# main.net
KiCad netlist of a schematic drawn in Altium Designer
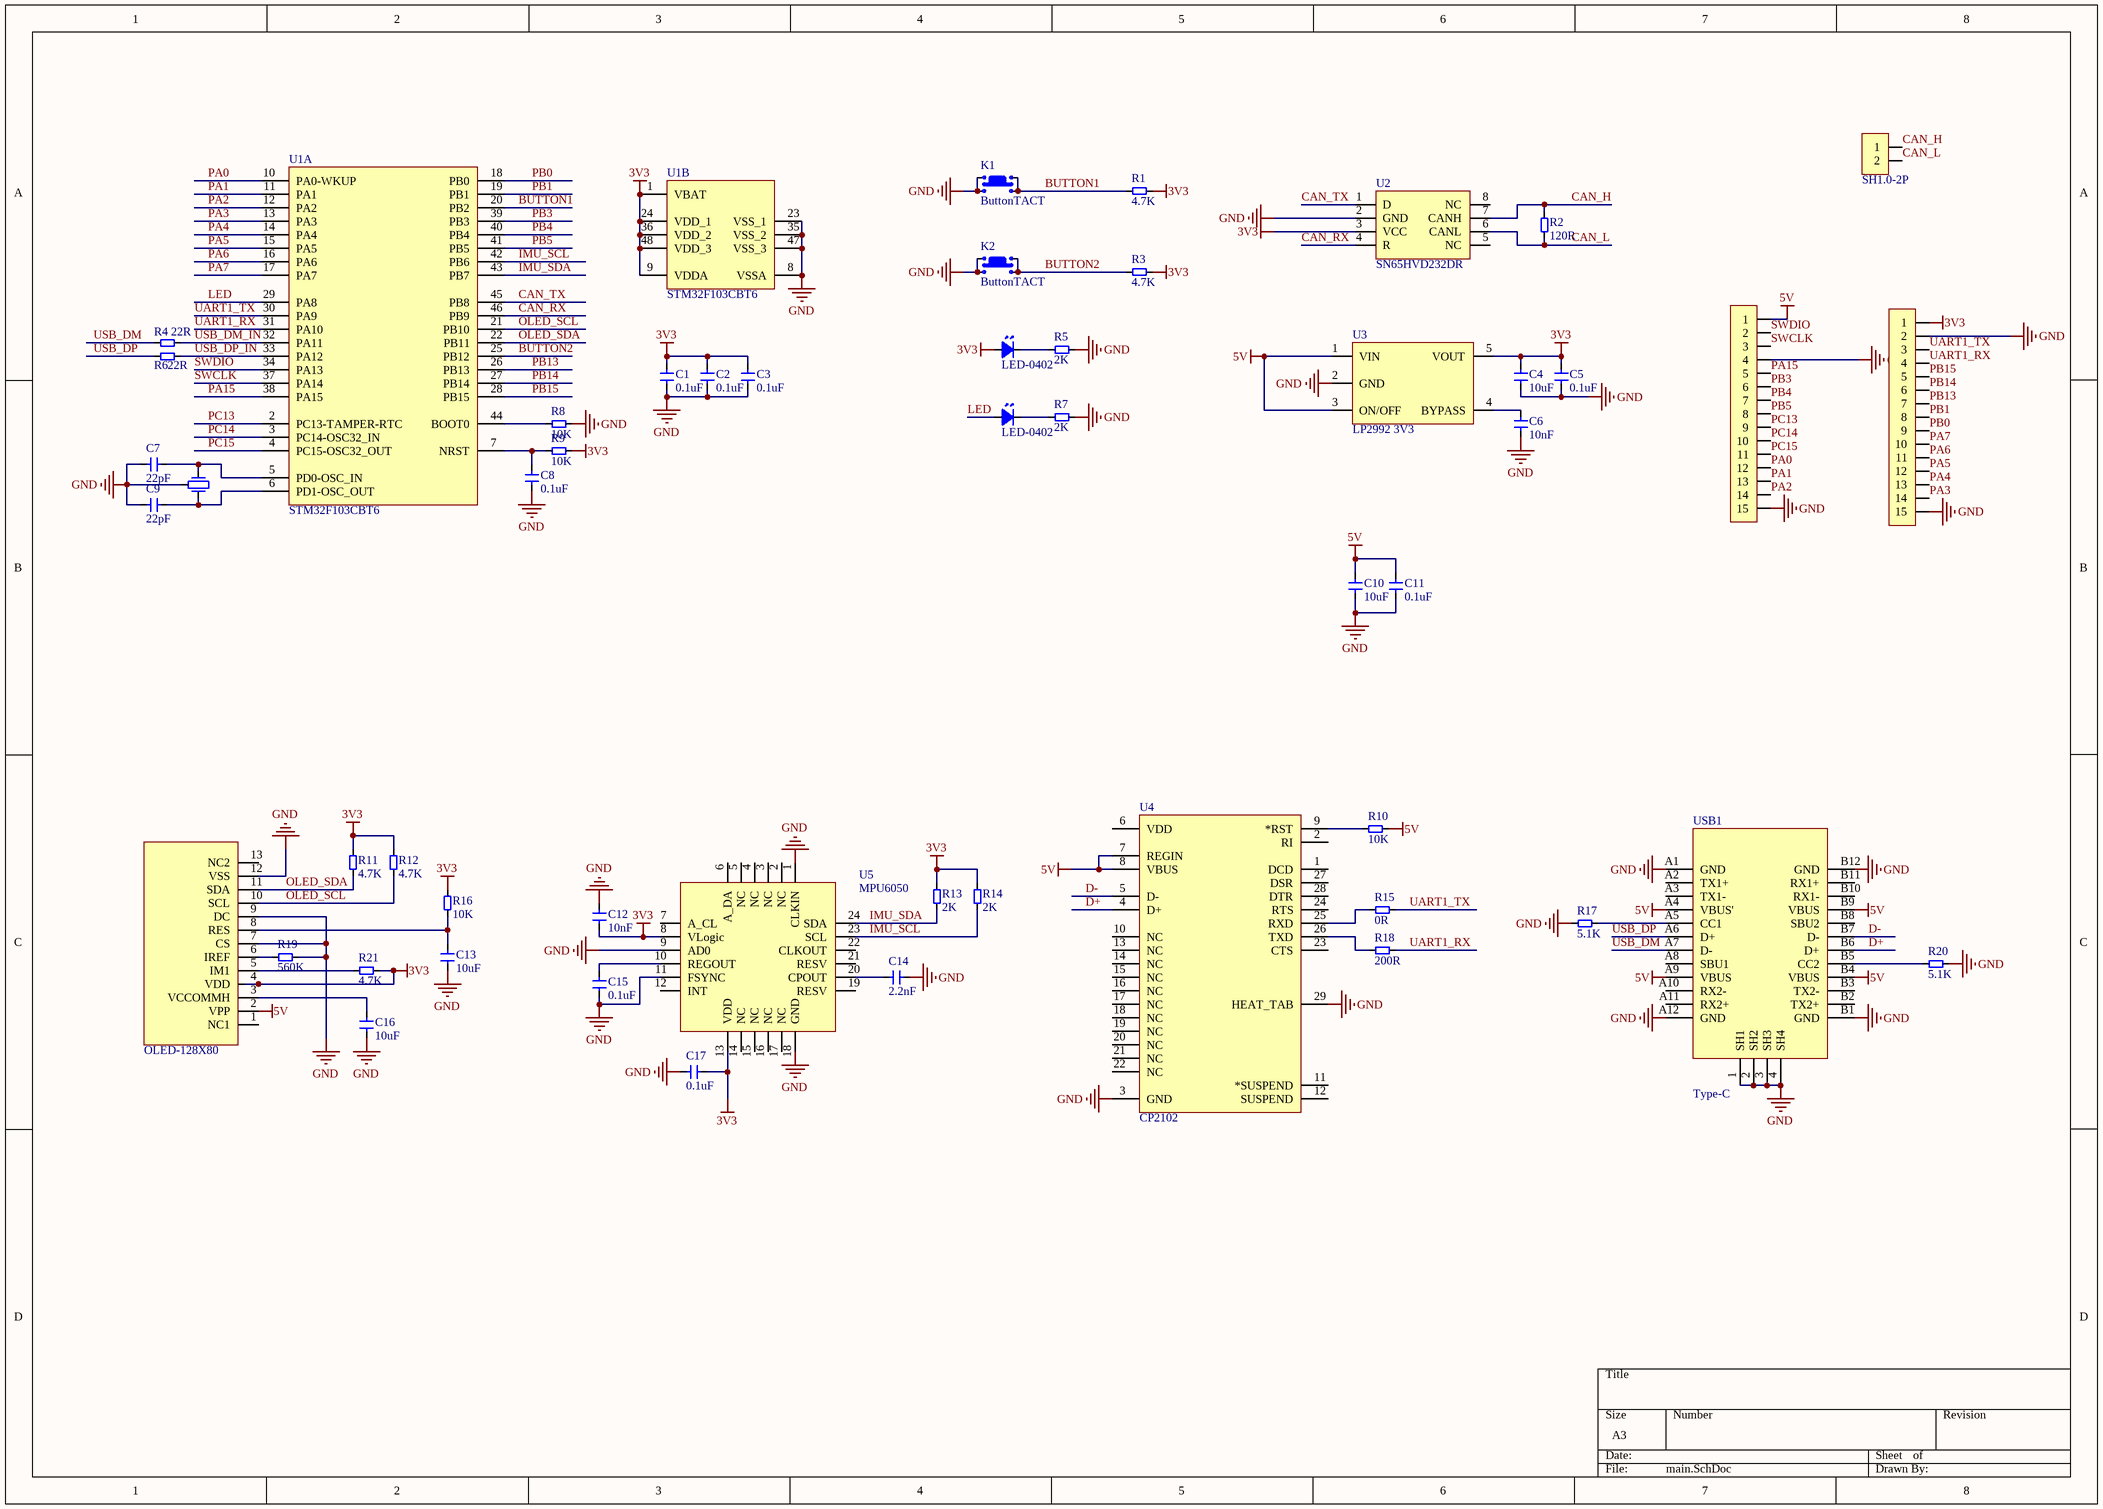
[diagram p0: main.SchDoc]

(export (version "E")
  (design (tool "Eeschema 10.0.6"))
  (components
    (comp (ref "*1")
      (value "SH1.0-2P")
      (footprint "SH1.0-2P")
      (libsource (lib "MySchlib1") (part "SH1.0-2P"))
    )
    (comp (ref "*2")
      (value "LED-0402")
      (footprint "LED_0402_YELLOW")
      (libsource (lib "MySchlib1") (part "LED-0402"))
    )
    (comp (ref "*3")
      (value "LED-0402")
      (footprint "LED_0402_YELLOW")
      (libsource (lib "MySchlib1") (part "LED-0402"))
    )
    (comp (ref "*4")
      (value "OSC-8MHz-3P")
      (footprint "晶振_3P")
      (libsource (lib "MySchlib1") (part "OSC-8MHz-3P"))
    )
    (comp (ref "*5")
      (value "HDR2.54-15P")
      (footprint "HDR2.54-15P")
      (libsource (lib "MySchlib1") (part "HDR2.54-15P"))
    )
    (comp (ref "*6")
      (value "HDR2.54-15P")
      (footprint "HDR2.54-15P")
      (libsource (lib "MySchlib1") (part "HDR2.54-15P"))
    )
    (comp (ref "1")
      (value "OLED-128X80")
      (footprint "OLED-128X80")
      (description "SH1107")
      (libsource (lib "MySchlib1") (part "OLED-128X80"))
    )
    (comp (ref "C1")
      (value "0.1uF")
      (footprint "CAP_0402")
      (description "Cap-0402")
      (libsource (lib "MySchlib1") (part "电容-0402"))
    )
    (comp (ref "C2")
      (value "0.1uF")
      (footprint "CAP_0402")
      (description "Cap-0402")
      (libsource (lib "MySchlib1") (part "电容-0402"))
    )
    (comp (ref "C3")
      (value "0.1uF")
      (footprint "CAP_0402")
      (description "Cap-0402")
      (libsource (lib "MySchlib1") (part "电容-0402"))
    )
    (comp (ref "C4")
      (value "10uF")
      (footprint "CAP_0402")
      (description "Cap-0402")
      (libsource (lib "MySchlib1") (part "电容-0402"))
    )
    (comp (ref "C5")
      (value "0.1uF")
      (footprint "CAP_0402")
      (description "Cap-0402")
      (libsource (lib "MySchlib1") (part "电容-0402"))
    )
    (comp (ref "C6")
      (value "10nF")
      (footprint "CAP_0402")
      (description "Cap-0402")
      (libsource (lib "MySchlib1") (part "电容-0402"))
    )
    (comp (ref "C7")
      (value "22pF")
      (footprint "CAP_0402")
      (description "Cap-0402")
      (libsource (lib "MySchlib1") (part "电容-0402"))
    )
    (comp (ref "C8")
      (value "0.1uF")
      (footprint "CAP_0402")
      (description "Cap-0402")
      (libsource (lib "MySchlib1") (part "电容-0402"))
    )
    (comp (ref "C9")
      (value "22pF")
      (footprint "CAP_0402")
      (description "Cap-0402")
      (libsource (lib "MySchlib1") (part "电容-0402"))
    )
    (comp (ref "C10")
      (value "10uF")
      (footprint "CAP_0402")
      (description "Cap-0402")
      (libsource (lib "MySchlib1") (part "电容-0402"))
    )
    (comp (ref "C11")
      (value "0.1uF")
      (footprint "CAP_0402")
      (description "Cap-0402")
      (libsource (lib "MySchlib1") (part "电容-0402"))
    )
    (comp (ref "C12")
      (value "10nF")
      (footprint "CAP_0402")
      (description "Cap-0402")
      (libsource (lib "MySchlib1") (part "电容-0402"))
    )
    (comp (ref "C13")
      (value "10uF")
      (footprint "CAP_0402")
      (description "Cap-0402")
      (libsource (lib "MySchlib1") (part "电容-0402"))
    )
    (comp (ref "C14")
      (value "2.2nF")
      (footprint "CAP_0402")
      (description "Cap-0402")
      (libsource (lib "MySchlib1") (part "电容-0402"))
    )
    (comp (ref "C15")
      (value "0.1uF")
      (footprint "CAP_0402")
      (description "Cap-0402")
      (libsource (lib "MySchlib1") (part "电容-0402"))
    )
    (comp (ref "C16")
      (value "10uF")
      (footprint "CAP_0402")
      (description "Cap-0402")
      (libsource (lib "MySchlib1") (part "电容-0402"))
    )
    (comp (ref "C17")
      (value "0.1uF")
      (footprint "CAP_0402")
      (description "Cap-0402")
      (libsource (lib "MySchlib1") (part "电容-0402"))
    )
    (comp (ref "K1")
      (value "ButtonTACT")
      (footprint "ButtonTACT_3.5*3.55_90")
      (libsource (lib "MySchlib1") (part "ButtonTACT"))
    )
    (comp (ref "K2")
      (value "ButtonTACT")
      (footprint "ButtonTACT_3.5*3.55_90")
      (libsource (lib "MySchlib1") (part "ButtonTACT"))
    )
    (comp (ref "R1")
      (value "4.7K")
      (footprint "RES_0402")
      (description "Res-0402")
      (libsource (lib "MySchlib1") (part "电阻-0402"))
    )
    (comp (ref "R2")
      (value "120R")
      (footprint "RES_0402")
      (description "Res-0402")
      (libsource (lib "MySchlib1") (part "电阻-0402"))
    )
    (comp (ref "R3")
      (value "4.7K")
      (footprint "RES_0402")
      (description "Res-0402")
      (libsource (lib "MySchlib1") (part "电阻-0402"))
    )
    (comp (ref "R4")
      (value "22R")
      (footprint "RES_0402")
      (description "Res-0402")
      (libsource (lib "MySchlib1") (part "电阻-0402"))
    )
    (comp (ref "R5")
      (value "2K")
      (footprint "RES_0402")
      (description "Res-0402")
      (libsource (lib "MySchlib1") (part "电阻-0402"))
    )
    (comp (ref "R6")
      (value "22R")
      (footprint "RES_0402")
      (description "Res-0402")
      (libsource (lib "MySchlib1") (part "电阻-0402"))
    )
    (comp (ref "R7")
      (value "2K")
      (footprint "RES_0402")
      (description "Res-0402")
      (libsource (lib "MySchlib1") (part "电阻-0402"))
    )
    (comp (ref "R8")
      (value "10K")
      (footprint "RES_0402")
      (description "Res-0402")
      (libsource (lib "MySchlib1") (part "电阻-0402"))
    )
    (comp (ref "R9")
      (value "10K")
      (footprint "RES_0402")
      (description "Res-0402")
      (libsource (lib "MySchlib1") (part "电阻-0402"))
    )
    (comp (ref "R10")
      (value "10K")
      (footprint "RES_0402")
      (description "Res-0402")
      (libsource (lib "MySchlib1") (part "电阻-0402"))
    )
    (comp (ref "R11")
      (value "4.7K")
      (footprint "RES_0402")
      (description "Res-0402")
      (libsource (lib "MySchlib1") (part "电阻-0402"))
    )
    (comp (ref "R12")
      (value "4.7K")
      (footprint "RES_0402")
      (description "Res-0402")
      (libsource (lib "MySchlib1") (part "电阻-0402"))
    )
    (comp (ref "R13")
      (value "2K")
      (footprint "RES_0402")
      (description "Res-0402")
      (libsource (lib "MySchlib1") (part "电阻-0402"))
    )
    (comp (ref "R14")
      (value "2K")
      (footprint "RES_0402")
      (description "Res-0402")
      (libsource (lib "MySchlib1") (part "电阻-0402"))
    )
    (comp (ref "R15")
      (value "0R")
      (footprint "RES_0402")
      (description "Res-0402")
      (libsource (lib "MySchlib1") (part "电阻-0402"))
    )
    (comp (ref "R16")
      (value "10K")
      (footprint "RES_0402")
      (description "Res-0402")
      (libsource (lib "MySchlib1") (part "电阻-0402"))
    )
    (comp (ref "R17")
      (value "5.1K")
      (footprint "RES_0402")
      (description "Res-0402")
      (libsource (lib "MySchlib1") (part "电阻-0402"))
    )
    (comp (ref "R18")
      (value "200R")
      (footprint "RES_0402")
      (description "Res-0402")
      (libsource (lib "MySchlib1") (part "电阻-0402"))
    )
    (comp (ref "R19")
      (value "560K")
      (footprint "RES_0402")
      (description "Res-0402")
      (libsource (lib "MySchlib1") (part "电阻-0402"))
    )
    (comp (ref "R20")
      (value "5.1K")
      (footprint "RES_0402")
      (description "Res-0402")
      (libsource (lib "MySchlib1") (part "电阻-0402"))
    )
    (comp (ref "R21")
      (value "4.7K")
      (footprint "RES_0402")
      (description "Res-0402")
      (libsource (lib "MySchlib1") (part "电阻-0402"))
    )
    (comp (ref "U1")
      (value "STM32F103CBT6")
      (footprint "LQFP-48")
      (libsource (lib "MySchlib1") (part "STM32F103CBT6"))
    )
    (comp (ref "U2")
      (value "SN65HVD232DR")
      (footprint "SO-8")
      (description "CAN通信")
      (libsource (lib "MySchlib1") (part "SN65HVD232DR"))
    )
    (comp (ref "U3")
      (value "LP2992 3V3")
      (footprint "SOT23-5")
      (description "LDO")
      (libsource (lib "MySchlib1") (part "LP2992 3V3"))
    )
    (comp (ref "U4") (value "CP2102") (footprint "QFN-28") (libsource (lib "MySchlib1") (part "CP2102")))
    (comp (ref "U5")
      (value "MPU6050")
      (footprint "QFN-24")
      (description "六轴陀螺仪")
      (libsource (lib "MySchlib1") (part "MPU6050"))
    )
    (comp (ref "USB1")
      (value "Type-C")
      (footprint "Type-C-TOP-16")
      (libsource (lib "MySchlib1") (part "Type-C"))
    )
  )
  (nets
    (net (code "1") (name "/BUTTON1") (class "Default")
      (node (ref "K1") (pin "2") (pinfunction "2_2") (pintype "passive"))
      (node (ref "K1") (pin "4") (pinfunction "4_4") (pintype "passive"))
      (node (ref "R1") (pin "1") (pinfunction "1_1") (pintype "passive"))
      (node (ref "U1") (pin "20") (pinfunction "PB2_20") (pintype "passive"))
    )
    (net (code "2") (name "/BUTTON2") (class "Default")
      (node (ref "K2") (pin "2") (pinfunction "2_2") (pintype "passive"))
      (node (ref "K2") (pin "4") (pinfunction "4_4") (pintype "passive"))
      (node (ref "R3") (pin "1") (pinfunction "1_1") (pintype "passive"))
      (node (ref "U1") (pin "25") (pinfunction "PB12_25") (pintype "passive"))
    )
    (net (code "3") (name "/CAN_H") (class "Default")
      (node (ref "*1") (pin "1") (pinfunction "1_1") (pintype "passive"))
      (node (ref "R2") (pin "2") (pinfunction "2_2") (pintype "passive"))
      (node (ref "U2") (pin "7") (pinfunction "CANH_7") (pintype "passive"))
    )
    (net (code "4") (name "/CAN_L") (class "Default")
      (node (ref "*1") (pin "2") (pinfunction "2_2") (pintype "passive"))
      (node (ref "R2") (pin "1") (pinfunction "1_1") (pintype "passive"))
      (node (ref "U2") (pin "6") (pinfunction "CANL_6") (pintype "passive"))
    )
    (net (code "5") (name "/CAN_RX") (class "Default")
      (node (ref "U1") (pin "46") (pinfunction "PB9_46") (pintype "passive"))
      (node (ref "U2") (pin "4") (pinfunction "R_4") (pintype "passive"))
    )
    (net (code "6") (name "/CAN_TX") (class "Default")
      (node (ref "U1") (pin "45") (pinfunction "PB8_45") (pintype "passive"))
      (node (ref "U2") (pin "1") (pinfunction "D_1") (pintype "passive"))
    )
    (net (code "7") (name "/D+") (class "Default")
      (node (ref "U4") (pin "4") (pinfunction "D+_4") (pintype "passive"))
      (node (ref "USB1") (pin "B6") (pinfunction "D+_B6") (pintype "passive"))
    )
    (net (code "8") (name "/D-") (class "Default")
      (node (ref "U4") (pin "5") (pinfunction "D-_5") (pintype "passive"))
      (node (ref "USB1") (pin "B7") (pinfunction "D-_B7") (pintype "passive"))
    )
    (net (code "9") (name "/IMU_SCL") (class "Default")
      (node (ref "R14") (pin "2") (pinfunction "2_2") (pintype "passive"))
      (node (ref "U1") (pin "42") (pinfunction "PB6_42") (pintype "passive"))
      (node (ref "U5") (pin "23") (pinfunction "SCL_23") (pintype "passive"))
    )
    (net (code "10") (name "/IMU_SDA") (class "Default")
      (node (ref "R13") (pin "1") (pinfunction "1_1") (pintype "passive"))
      (node (ref "U1") (pin "43") (pinfunction "PB7_43") (pintype "passive"))
      (node (ref "U5") (pin "24") (pinfunction "SDA_24") (pintype "passive"))
    )
    (net (code "11") (name "/LED") (class "Default")
      (node (ref "*3") (pin "1") (pinfunction "1_1") (pintype "passive"))
      (node (ref "U1") (pin "29") (pinfunction "PA8_29") (pintype "passive"))
    )
    (net (code "12") (name "/OLED_SCL") (class "Default")
      (node (ref "1") (pin "10") (pinfunction "SCL_10") (pintype "passive"))
      (node (ref "R12") (pin "2") (pinfunction "2_2") (pintype "passive"))
      (node (ref "U1") (pin "21") (pinfunction "PB10_21") (pintype "passive"))
    )
    (net (code "13") (name "/OLED_SDA") (class "Default")
      (node (ref "1") (pin "11") (pinfunction "SDA_11") (pintype "passive"))
      (node (ref "R11") (pin "2") (pinfunction "2_2") (pintype "passive"))
      (node (ref "U1") (pin "22") (pinfunction "PB11_22") (pintype "passive"))
    )
    (net (code "14") (name "/PA0") (class "Default")
      (node (ref "*5") (pin "12") (pinfunction "12_12") (pintype "passive"))
      (node (ref "U1") (pin "10") (pinfunction "PA0-WKUP_10") (pintype "passive"))
    )
    (net (code "15") (name "/PA1") (class "Default")
      (node (ref "*5") (pin "13") (pinfunction "13_13") (pintype "passive"))
      (node (ref "U1") (pin "11") (pinfunction "PA1_11") (pintype "passive"))
    )
    (net (code "16") (name "/PA2") (class "Default")
      (node (ref "*5") (pin "14") (pinfunction "14_14") (pintype "passive"))
      (node (ref "U1") (pin "12") (pinfunction "PA2_12") (pintype "passive"))
    )
    (net (code "17") (name "/PA3") (class "Default")
      (node (ref "*6") (pin "14") (pinfunction "14_14") (pintype "passive"))
      (node (ref "U1") (pin "13") (pinfunction "PA3_13") (pintype "passive"))
    )
    (net (code "18") (name "/PA4") (class "Default")
      (node (ref "*6") (pin "13") (pinfunction "13_13") (pintype "passive"))
      (node (ref "U1") (pin "14") (pinfunction "PA4_14") (pintype "passive"))
    )
    (net (code "19") (name "/PA5") (class "Default")
      (node (ref "*6") (pin "12") (pinfunction "12_12") (pintype "passive"))
      (node (ref "U1") (pin "15") (pinfunction "PA5_15") (pintype "passive"))
    )
    (net (code "20") (name "/PA6") (class "Default")
      (node (ref "*6") (pin "11") (pinfunction "11_11") (pintype "passive"))
      (node (ref "U1") (pin "16") (pinfunction "PA6_16") (pintype "passive"))
    )
    (net (code "21") (name "/PA7") (class "Default")
      (node (ref "*6") (pin "10") (pinfunction "10_10") (pintype "passive"))
      (node (ref "U1") (pin "17") (pinfunction "PA7_17") (pintype "passive"))
    )
    (net (code "22") (name "/PA15") (class "Default")
      (node (ref "*5") (pin "5") (pinfunction "5_5") (pintype "passive"))
      (node (ref "U1") (pin "38") (pinfunction "PA15_38") (pintype "passive"))
    )
    (net (code "23") (name "/PB0") (class "Default")
      (node (ref "*6") (pin "9") (pinfunction "9_9") (pintype "passive"))
      (node (ref "U1") (pin "18") (pinfunction "PB0_18") (pintype "passive"))
    )
    (net (code "24") (name "/PB1") (class "Default")
      (node (ref "*6") (pin "8") (pinfunction "8_8") (pintype "passive"))
      (node (ref "U1") (pin "19") (pinfunction "PB1_19") (pintype "passive"))
    )
    (net (code "25") (name "/PB3") (class "Default")
      (node (ref "*5") (pin "6") (pinfunction "6_6") (pintype "passive"))
      (node (ref "U1") (pin "39") (pinfunction "PB3_39") (pintype "passive"))
    )
    (net (code "26") (name "/PB4") (class "Default")
      (node (ref "*5") (pin "7") (pinfunction "7_7") (pintype "passive"))
      (node (ref "U1") (pin "40") (pinfunction "PB4_40") (pintype "passive"))
    )
    (net (code "27") (name "/PB5") (class "Default")
      (node (ref "*5") (pin "8") (pinfunction "8_8") (pintype "passive"))
      (node (ref "U1") (pin "41") (pinfunction "PB5_41") (pintype "passive"))
    )
    (net (code "28") (name "/PB13") (class "Default")
      (node (ref "*6") (pin "7") (pinfunction "7_7") (pintype "passive"))
      (node (ref "U1") (pin "26") (pinfunction "PB13_26") (pintype "passive"))
    )
    (net (code "29") (name "/PB14") (class "Default")
      (node (ref "*6") (pin "6") (pinfunction "6_6") (pintype "passive"))
      (node (ref "U1") (pin "27") (pinfunction "PB14_27") (pintype "passive"))
    )
    (net (code "30") (name "/PB15") (class "Default")
      (node (ref "*6") (pin "5") (pinfunction "5_5") (pintype "passive"))
      (node (ref "U1") (pin "28") (pinfunction "PB15_28") (pintype "passive"))
    )
    (net (code "31") (name "/PC13") (class "Default")
      (node (ref "*5") (pin "9") (pinfunction "9_9") (pintype "passive"))
      (node (ref "U1") (pin "2") (pinfunction "PC13-TAMPER-RTC_2") (pintype "passive"))
    )
    (net (code "32") (name "/PC14") (class "Default")
      (node (ref "*5") (pin "10") (pinfunction "10_10") (pintype "passive"))
      (node (ref "U1") (pin "3") (pinfunction "PC14-OSC32_IN_3") (pintype "passive"))
    )
    (net (code "33") (name "/PC15") (class "Default")
      (node (ref "*5") (pin "11") (pinfunction "11_11") (pintype "passive"))
      (node (ref "U1") (pin "4") (pinfunction "PC15-OSC32_OUT_4") (pintype "passive"))
    )
    (net (code "34") (name "/SWCLK") (class "Default")
      (node (ref "*5") (pin "3") (pinfunction "3_3") (pintype "passive"))
      (node (ref "U1") (pin "37") (pinfunction "PA14_37") (pintype "passive"))
    )
    (net (code "35") (name "/SWDIO") (class "Default")
      (node (ref "*5") (pin "2") (pinfunction "2_2") (pintype "passive"))
      (node (ref "U1") (pin "34") (pinfunction "PA13_34") (pintype "passive"))
    )
    (net (code "36") (name "/UART1_RX") (class "Default")
      (node (ref "*6") (pin "4") (pinfunction "4_4") (pintype "passive"))
      (node (ref "R18") (pin "2") (pinfunction "2_2") (pintype "passive"))
      (node (ref "U1") (pin "31") (pinfunction "PA10_31") (pintype "passive"))
    )
    (net (code "37") (name "/UART1_TX") (class "Default")
      (node (ref "*6") (pin "3") (pinfunction "3_3") (pintype "passive"))
      (node (ref "R15") (pin "2") (pinfunction "2_2") (pintype "passive"))
      (node (ref "U1") (pin "30") (pinfunction "PA9_30") (pintype "passive"))
    )
    (net (code "38") (name "/USB_DM") (class "Default")
      (node (ref "R4") (pin "1") (pinfunction "1_1") (pintype "passive"))
      (node (ref "USB1") (pin "A7") (pinfunction "D-_A7") (pintype "passive"))
    )
    (net (code "39") (name "/USB_DM_IN") (class "Default")
      (node (ref "R4") (pin "2") (pinfunction "2_2") (pintype "passive"))
      (node (ref "U1") (pin "32") (pinfunction "PA11_32") (pintype "passive"))
    )
    (net (code "40") (name "/USB_DP") (class "Default")
      (node (ref "R6") (pin "1") (pinfunction "1_1") (pintype "passive"))
      (node (ref "USB1") (pin "A6") (pinfunction "D+_A6") (pintype "passive"))
    )
    (net (code "41") (name "/USB_DP_IN") (class "Default")
      (node (ref "R6") (pin "2") (pinfunction "2_2") (pintype "passive"))
      (node (ref "U1") (pin "33") (pinfunction "PA12_33") (pintype "passive"))
    )
    (net (code "42") (name "3V3") (class "Default")
      (node (ref "*2") (pin "1") (pinfunction "1_1") (pintype "passive"))
      (node (ref "*6") (pin "1") (pinfunction "1_1") (pintype "passive"))
      (node (ref "1") (pin "4") (pinfunction "VDD_4") (pintype "passive"))
      (node (ref "C1") (pin "2") (pinfunction "2_2") (pintype "passive"))
      (node (ref "C12") (pin "1") (pinfunction "1_1") (pintype "passive"))
      (node (ref "C17") (pin "1") (pinfunction "1_1") (pintype "passive"))
      (node (ref "C2") (pin "2") (pinfunction "2_2") (pintype "passive"))
      (node (ref "C3") (pin "2") (pinfunction "2_2") (pintype "passive"))
      (node (ref "C4") (pin "2") (pinfunction "2_2") (pintype "passive"))
      (node (ref "C5") (pin "2") (pinfunction "2_2") (pintype "passive"))
      (node (ref "R1") (pin "2") (pinfunction "2_2") (pintype "passive"))
      (node (ref "R11") (pin "1") (pinfunction "1_1") (pintype "passive"))
      (node (ref "R12") (pin "1") (pinfunction "1_1") (pintype "passive"))
      (node (ref "R13") (pin "2") (pinfunction "2_2") (pintype "passive"))
      (node (ref "R14") (pin "1") (pinfunction "1_1") (pintype "passive"))
      (node (ref "R16") (pin "2") (pinfunction "2_2") (pintype "passive"))
      (node (ref "R21") (pin "2") (pinfunction "2_2") (pintype "passive"))
      (node (ref "R3") (pin "2") (pinfunction "2_2") (pintype "passive"))
      (node (ref "R9") (pin "2") (pinfunction "2_2") (pintype "passive"))
      (node (ref "U1") (pin "1") (pinfunction "VBAT_1") (pintype "passive"))
      (node (ref "U1") (pin "24") (pinfunction "VDD_1_24") (pintype "passive"))
      (node (ref "U1") (pin "36") (pinfunction "VDD_2_36") (pintype "passive"))
      (node (ref "U1") (pin "48") (pinfunction "VDD_3_48") (pintype "passive"))
      (node (ref "U1") (pin "9") (pinfunction "VDDA_9") (pintype "passive"))
      (node (ref "U2") (pin "3") (pinfunction "VCC_3") (pintype "passive"))
      (node (ref "U3") (pin "5") (pinfunction "VOUT_5") (pintype "passive"))
      (node (ref "U5") (pin "13") (pinfunction "VDD_13") (pintype "passive"))
      (node (ref "U5") (pin "8") (pinfunction "VLogic_8") (pintype "passive"))
    )
    (net (code "43") (name "5V") (class "Default")
      (node (ref "*5") (pin "1") (pinfunction "1_1") (pintype "passive"))
      (node (ref "1") (pin "2") (pinfunction "VPP_2") (pintype "passive"))
      (node (ref "C10") (pin "2") (pinfunction "2_2") (pintype "passive"))
      (node (ref "C11") (pin "2") (pinfunction "2_2") (pintype "passive"))
      (node (ref "R10") (pin "2") (pinfunction "2_2") (pintype "passive"))
      (node (ref "U3") (pin "1") (pinfunction "VIN_1") (pintype "passive"))
      (node (ref "U3") (pin "3") (pinfunction "ON/OFF_3") (pintype "passive"))
      (node (ref "U4") (pin "7") (pinfunction "REGIN_7") (pintype "passive"))
      (node (ref "U4") (pin "8") (pinfunction "VBUS_8") (pintype "passive"))
      (node (ref "USB1") (pin "A4") (pinfunction "VBUS'_A4") (pintype "passive"))
      (node (ref "USB1") (pin "A9") (pinfunction "VBUS_A9") (pintype "passive"))
      (node (ref "USB1") (pin "B4") (pinfunction "VBUS_B4") (pintype "passive"))
      (node (ref "USB1") (pin "B9") (pinfunction "VBUS_B9") (pintype "passive"))
    )
    (net (code "44") (name "GND") (class "Default")
      (node (ref "*4") (pin "2") (pinfunction "2_2") (pintype "passive"))
      (node (ref "*5") (pin "15") (pinfunction "15_15") (pintype "passive"))
      (node (ref "*5") (pin "4") (pinfunction "4_4") (pintype "passive"))
      (node (ref "*6") (pin "15") (pinfunction "15_15") (pintype "passive"))
      (node (ref "*6") (pin "2") (pinfunction "2_2") (pintype "passive"))
      (node (ref "1") (pin "12") (pinfunction "VSS_12") (pintype "passive"))
      (node (ref "1") (pin "7") (pinfunction "CS_7") (pintype "passive"))
      (node (ref "1") (pin "9") (pinfunction "DC_9") (pintype "passive"))
      (node (ref "C1") (pin "1") (pinfunction "1_1") (pintype "passive"))
      (node (ref "C10") (pin "1") (pinfunction "1_1") (pintype "passive"))
      (node (ref "C11") (pin "1") (pinfunction "1_1") (pintype "passive"))
      (node (ref "C12") (pin "2") (pinfunction "2_2") (pintype "passive"))
      (node (ref "C13") (pin "1") (pinfunction "1_1") (pintype "passive"))
      (node (ref "C14") (pin "1") (pinfunction "1_1") (pintype "passive"))
      (node (ref "C15") (pin "2") (pinfunction "2_2") (pintype "passive"))
      (node (ref "C16") (pin "1") (pinfunction "1_1") (pintype "passive"))
      (node (ref "C17") (pin "2") (pinfunction "2_2") (pintype "passive"))
      (node (ref "C2") (pin "1") (pinfunction "1_1") (pintype "passive"))
      (node (ref "C3") (pin "1") (pinfunction "1_1") (pintype "passive"))
      (node (ref "C4") (pin "1") (pinfunction "1_1") (pintype "passive"))
      (node (ref "C5") (pin "1") (pinfunction "1_1") (pintype "passive"))
      (node (ref "C6") (pin "1") (pinfunction "1_1") (pintype "passive"))
      (node (ref "C7") (pin "2") (pinfunction "2_2") (pintype "passive"))
      (node (ref "C8") (pin "2") (pinfunction "2_2") (pintype "passive"))
      (node (ref "C9") (pin "2") (pinfunction "2_2") (pintype "passive"))
      (node (ref "K1") (pin "1") (pinfunction "1_1") (pintype "passive"))
      (node (ref "K1") (pin "3") (pinfunction "3_3") (pintype "passive"))
      (node (ref "K2") (pin "1") (pinfunction "1_1") (pintype "passive"))
      (node (ref "K2") (pin "3") (pinfunction "3_3") (pintype "passive"))
      (node (ref "R17") (pin "1") (pinfunction "1_1") (pintype "passive"))
      (node (ref "R19") (pin "2") (pinfunction "2_2") (pintype "passive"))
      (node (ref "R20") (pin "2") (pinfunction "2_2") (pintype "passive"))
      (node (ref "R5") (pin "2") (pinfunction "2_2") (pintype "passive"))
      (node (ref "R7") (pin "2") (pinfunction "2_2") (pintype "passive"))
      (node (ref "R8") (pin "2") (pinfunction "2_2") (pintype "passive"))
      (node (ref "U1") (pin "23") (pinfunction "VSS_1_23") (pintype "passive"))
      (node (ref "U1") (pin "35") (pinfunction "VSS_2_35") (pintype "passive"))
      (node (ref "U1") (pin "47") (pinfunction "VSS_3_47") (pintype "passive"))
      (node (ref "U1") (pin "8") (pinfunction "VSSA_8") (pintype "passive"))
      (node (ref "U2") (pin "2") (pinfunction "GND_2") (pintype "passive"))
      (node (ref "U3") (pin "2") (pinfunction "GND_2") (pintype "passive"))
      (node (ref "U4") (pin "29") (pinfunction "HEAT_TAB_29") (pintype "passive"))
      (node (ref "U4") (pin "3") (pinfunction "GND_3") (pintype "passive"))
      (node (ref "U5") (pin "1") (pinfunction "CLKIN_1") (pintype "passive"))
      (node (ref "U5") (pin "11") (pinfunction "FSYNC_11") (pintype "passive"))
      (node (ref "U5") (pin "18") (pinfunction "GND_18") (pintype "passive"))
      (node (ref "U5") (pin "9") (pinfunction "AD0_9") (pintype "passive"))
      (node (ref "USB1") (pin "1") (pinfunction "SH1_1") (pintype "passive"))
      (node (ref "USB1") (pin "2") (pinfunction "SH2_2") (pintype "passive"))
      (node (ref "USB1") (pin "3") (pinfunction "SH3_3") (pintype "passive"))
      (node (ref "USB1") (pin "4") (pinfunction "SH4_4") (pintype "passive"))
      (node (ref "USB1") (pin "A1") (pinfunction "GND_A1") (pintype "passive"))
      (node (ref "USB1") (pin "A12") (pinfunction "GND_A12") (pintype "passive"))
      (node (ref "USB1") (pin "B1") (pinfunction "GND_B1") (pintype "passive"))
      (node (ref "USB1") (pin "B12") (pinfunction "GND_B12") (pintype "passive"))
    )
    (net (code "45") (name "Net-(*2-Pad2)") (class "Default")
      (node (ref "*2") (pin "2") (pinfunction "2_2") (pintype "passive"))
      (node (ref "R5") (pin "1") (pinfunction "1_1") (pintype "passive"))
    )
    (net (code "46") (name "Net-(*3-Pad2)") (class "Default")
      (node (ref "*3") (pin "2") (pinfunction "2_2") (pintype "passive"))
      (node (ref "R7") (pin "1") (pinfunction "1_1") (pintype "passive"))
    )
    (net (code "47") (name "Net-(1-IM1)") (class "Default")
      (node (ref "1") (pin "5") (pinfunction "IM1_5") (pintype "passive"))
      (node (ref "R21") (pin "1") (pinfunction "1_1") (pintype "passive"))
    )
    (net (code "48") (name "Net-(1-IREF)") (class "Default")
      (node (ref "1") (pin "6") (pinfunction "IREF_6") (pintype "passive"))
      (node (ref "R19") (pin "1") (pinfunction "1_1") (pintype "passive"))
    )
    (net (code "49") (name "Net-(1-RES)") (class "Default")
      (node (ref "1") (pin "8") (pinfunction "RES_8") (pintype "passive"))
      (node (ref "C13") (pin "2") (pinfunction "2_2") (pintype "passive"))
      (node (ref "R16") (pin "1") (pinfunction "1_1") (pintype "passive"))
    )
    (net (code "50") (name "Net-(1-VCCOMMH)") (class "Default")
      (node (ref "1") (pin "3") (pinfunction "VCCOMMH_3") (pintype "passive"))
      (node (ref "C16") (pin "2") (pinfunction "2_2") (pintype "passive"))
    )
    (net (code "51") (name "Net-(U1A-BOOT0)") (class "Default")
      (node (ref "R8") (pin "1") (pinfunction "1_1") (pintype "passive"))
      (node (ref "U1") (pin "44") (pinfunction "BOOT0_44") (pintype "passive"))
    )
    (net (code "52") (name "Net-(U1A-NRST)") (class "Default")
      (node (ref "C8") (pin "1") (pinfunction "1_1") (pintype "passive"))
      (node (ref "R9") (pin "1") (pinfunction "1_1") (pintype "passive"))
      (node (ref "U1") (pin "7") (pinfunction "NRST_7") (pintype "passive"))
    )
    (net (code "53") (name "Net-(U1A-PD0-OSC_IN)") (class "Default")
      (node (ref "*4") (pin "3") (pinfunction "3_3") (pintype "passive"))
      (node (ref "C7") (pin "1") (pinfunction "1_1") (pintype "passive"))
      (node (ref "U1") (pin "5") (pinfunction "PD0-OSC_IN_5") (pintype "passive"))
    )
    (net (code "54") (name "Net-(U1A-PD1-OSC_OUT)") (class "Default")
      (node (ref "*4") (pin "1") (pinfunction "1_1") (pintype "passive"))
      (node (ref "C9") (pin "1") (pinfunction "1_1") (pintype "passive"))
      (node (ref "U1") (pin "6") (pinfunction "PD1-OSC_OUT_6") (pintype "passive"))
    )
    (net (code "55") (name "Net-(U3-BYPASS)") (class "Default")
      (node (ref "C6") (pin "2") (pinfunction "2_2") (pintype "passive"))
      (node (ref "U3") (pin "4") (pinfunction "BYPASS_4") (pintype "passive"))
    )
    (net (code "56") (name "Net-(U4-*RST)") (class "Default")
      (node (ref "R10") (pin "1") (pinfunction "1_1") (pintype "passive"))
      (node (ref "U4") (pin "9") (pinfunction "*RST_9") (pintype "passive"))
    )
    (net (code "57") (name "Net-(U4-RXD)") (class "Default")
      (node (ref "R15") (pin "1") (pinfunction "1_1") (pintype "passive"))
      (node (ref "U4") (pin "25") (pinfunction "RXD_25") (pintype "passive"))
    )
    (net (code "58") (name "Net-(U4-TXD)") (class "Default")
      (node (ref "R18") (pin "1") (pinfunction "1_1") (pintype "passive"))
      (node (ref "U4") (pin "26") (pinfunction "TXD_26") (pintype "passive"))
    )
    (net (code "59") (name "Net-(U5-CPOUT)") (class "Default")
      (node (ref "C14") (pin "2") (pinfunction "2_2") (pintype "passive"))
      (node (ref "U5") (pin "20") (pinfunction "CPOUT_20") (pintype "passive"))
    )
    (net (code "60") (name "Net-(U5-REGOUT)") (class "Default")
      (node (ref "C15") (pin "1") (pinfunction "1_1") (pintype "passive"))
      (node (ref "U5") (pin "10") (pinfunction "REGOUT_10") (pintype "passive"))
    )
    (net (code "61") (name "Net-(USB1-CC1)") (class "Default")
      (node (ref "R17") (pin "2") (pinfunction "2_2") (pintype "passive"))
      (node (ref "USB1") (pin "A5") (pinfunction "CC1_A5") (pintype "passive"))
    )
    (net (code "62") (name "Net-(USB1-CC2)") (class "Default")
      (node (ref "R20") (pin "1") (pinfunction "1_1") (pintype "passive"))
      (node (ref "USB1") (pin "B5") (pinfunction "CC2_B5") (pintype "passive"))
    )
    (net (code "63") (name "unconnected-(1-NC1-Pad1)") (class "Default")
      (node (ref "1") (pin "1") (pinfunction "NC1_1") (pintype "passive"))
    )
    (net (code "64") (name "unconnected-(1-NC2-Pad13)") (class "Default")
      (node (ref "1") (pin "13") (pinfunction "NC2_13") (pintype "passive"))
    )
    (net (code "65") (name "unconnected-(U2-NC-Pad5)") (class "Default")
      (node (ref "U2") (pin "5") (pinfunction "NC_5") (pintype "passive"))
    )
    (net (code "66") (name "unconnected-(U2-NC-Pad8)") (class "Default")
      (node (ref "U2") (pin "8") (pinfunction "NC_8") (pintype "passive"))
    )
    (net (code "67") (name "unconnected-(U4-*SUSPEND-Pad11)") (class "Default")
      (node (ref "U4") (pin "11") (pinfunction "*SUSPEND_11") (pintype "passive"))
    )
    (net (code "68") (name "unconnected-(U4-CTS-Pad23)") (class "Default")
      (node (ref "U4") (pin "23") (pinfunction "CTS_23") (pintype "passive"))
    )
    (net (code "69") (name "unconnected-(U4-DCD-Pad1)") (class "Default")
      (node (ref "U4") (pin "1") (pinfunction "DCD_1") (pintype "passive"))
    )
    (net (code "70") (name "unconnected-(U4-DSR-Pad27)") (class "Default")
      (node (ref "U4") (pin "27") (pinfunction "DSR_27") (pintype "passive"))
    )
    (net (code "71") (name "unconnected-(U4-DTR-Pad28)") (class "Default")
      (node (ref "U4") (pin "28") (pinfunction "DTR_28") (pintype "passive"))
    )
    (net (code "72") (name "unconnected-(U4-NC-Pad10)") (class "Default")
      (node (ref "U4") (pin "10") (pinfunction "NC_10") (pintype "passive"))
    )
    (net (code "73") (name "unconnected-(U4-NC-Pad13)") (class "Default")
      (node (ref "U4") (pin "13") (pinfunction "NC_13") (pintype "passive"))
    )
    (net (code "74") (name "unconnected-(U4-NC-Pad14)") (class "Default")
      (node (ref "U4") (pin "14") (pinfunction "NC_14") (pintype "passive"))
    )
    (net (code "75") (name "unconnected-(U4-NC-Pad15)") (class "Default")
      (node (ref "U4") (pin "15") (pinfunction "NC_15") (pintype "passive"))
    )
    (net (code "76") (name "unconnected-(U4-NC-Pad16)") (class "Default")
      (node (ref "U4") (pin "16") (pinfunction "NC_16") (pintype "passive"))
    )
    (net (code "77") (name "unconnected-(U4-NC-Pad17)") (class "Default")
      (node (ref "U4") (pin "17") (pinfunction "NC_17") (pintype "passive"))
    )
    (net (code "78") (name "unconnected-(U4-NC-Pad18)") (class "Default")
      (node (ref "U4") (pin "18") (pinfunction "NC_18") (pintype "passive"))
    )
    (net (code "79") (name "unconnected-(U4-NC-Pad19)") (class "Default")
      (node (ref "U4") (pin "19") (pinfunction "NC_19") (pintype "passive"))
    )
    (net (code "80") (name "unconnected-(U4-NC-Pad20)") (class "Default")
      (node (ref "U4") (pin "20") (pinfunction "NC_20") (pintype "passive"))
    )
    (net (code "81") (name "unconnected-(U4-NC-Pad21)") (class "Default")
      (node (ref "U4") (pin "21") (pinfunction "NC_21") (pintype "passive"))
    )
    (net (code "82") (name "unconnected-(U4-NC-Pad22)") (class "Default")
      (node (ref "U4") (pin "22") (pinfunction "NC_22") (pintype "passive"))
    )
    (net (code "83") (name "unconnected-(U4-RI-Pad2)") (class "Default")
      (node (ref "U4") (pin "2") (pinfunction "RI_2") (pintype "passive"))
    )
    (net (code "84") (name "unconnected-(U4-RTS-Pad24)") (class "Default")
      (node (ref "U4") (pin "24") (pinfunction "RTS_24") (pintype "passive"))
    )
    (net (code "85") (name "unconnected-(U4-SUSPEND-Pad12)") (class "Default")
      (node (ref "U4") (pin "12") (pinfunction "SUSPEND_12") (pintype "passive"))
    )
    (net (code "86") (name "unconnected-(U4-VDD-Pad6)") (class "Default")
      (node (ref "U4") (pin "6") (pinfunction "VDD_6") (pintype "passive"))
    )
    (net (code "87") (name "unconnected-(U5-A_CL-Pad7)") (class "Default")
      (node (ref "U5") (pin "7") (pinfunction "A_CL_7") (pintype "passive"))
    )
    (net (code "88") (name "unconnected-(U5-A_DA-Pad6)") (class "Default")
      (node (ref "U5") (pin "6") (pinfunction "A_DA_6") (pintype "passive"))
    )
    (net (code "89") (name "unconnected-(U5-CLKOUT-Pad22)") (class "Default")
      (node (ref "U5") (pin "22") (pinfunction "CLKOUT_22") (pintype "passive"))
    )
    (net (code "90") (name "unconnected-(U5-INT-Pad12)") (class "Default")
      (node (ref "U5") (pin "12") (pinfunction "INT_12") (pintype "passive"))
    )
    (net (code "91") (name "unconnected-(U5-NC-Pad2)") (class "Default")
      (node (ref "U5") (pin "2") (pinfunction "NC_2") (pintype "passive"))
    )
    (net (code "92") (name "unconnected-(U5-NC-Pad3)") (class "Default")
      (node (ref "U5") (pin "3") (pinfunction "NC_3") (pintype "passive"))
    )
    (net (code "93") (name "unconnected-(U5-NC-Pad4)") (class "Default")
      (node (ref "U5") (pin "4") (pinfunction "NC_4") (pintype "passive"))
    )
    (net (code "94") (name "unconnected-(U5-NC-Pad5)") (class "Default")
      (node (ref "U5") (pin "5") (pinfunction "NC_5") (pintype "passive"))
    )
    (net (code "95") (name "unconnected-(U5-NC-Pad14)") (class "Default")
      (node (ref "U5") (pin "14") (pinfunction "NC_14") (pintype "passive"))
    )
    (net (code "96") (name "unconnected-(U5-NC-Pad15)") (class "Default")
      (node (ref "U5") (pin "15") (pinfunction "NC_15") (pintype "passive"))
    )
    (net (code "97") (name "unconnected-(U5-NC-Pad16)") (class "Default")
      (node (ref "U5") (pin "16") (pinfunction "NC_16") (pintype "passive"))
    )
    (net (code "98") (name "unconnected-(U5-NC-Pad17)") (class "Default")
      (node (ref "U5") (pin "17") (pinfunction "NC_17") (pintype "passive"))
    )
    (net (code "99") (name "unconnected-(U5-RESV-Pad19)") (class "Default")
      (node (ref "U5") (pin "19") (pinfunction "RESV_19") (pintype "passive"))
    )
    (net (code "100") (name "unconnected-(U5-RESV-Pad21)") (class "Default")
      (node (ref "U5") (pin "21") (pinfunction "RESV_21") (pintype "passive"))
    )
    (net (code "101") (name "unconnected-(USB1-RX1+-PadB11)") (class "Default")
      (node (ref "USB1") (pin "B11") (pinfunction "RX1+_B11") (pintype "passive"))
    )
    (net (code "102") (name "unconnected-(USB1-RX1--PadB10)") (class "Default")
      (node (ref "USB1") (pin "B10") (pinfunction "RX1-_B10") (pintype "passive"))
    )
    (net (code "103") (name "unconnected-(USB1-RX2+-PadA11)") (class "Default")
      (node (ref "USB1") (pin "A11") (pinfunction "RX2+_A11") (pintype "passive"))
    )
    (net (code "104") (name "unconnected-(USB1-RX2--PadA10)") (class "Default")
      (node (ref "USB1") (pin "A10") (pinfunction "RX2-_A10") (pintype "passive"))
    )
    (net (code "105") (name "unconnected-(USB1-SBU1-PadA8)") (class "Default")
      (node (ref "USB1") (pin "A8") (pinfunction "SBU1_A8") (pintype "passive"))
    )
    (net (code "106") (name "unconnected-(USB1-SBU2-PadB8)") (class "Default")
      (node (ref "USB1") (pin "B8") (pinfunction "SBU2_B8") (pintype "passive"))
    )
    (net (code "107") (name "unconnected-(USB1-TX1+-PadA2)") (class "Default")
      (node (ref "USB1") (pin "A2") (pinfunction "TX1+_A2") (pintype "passive"))
    )
    (net (code "108") (name "unconnected-(USB1-TX1--PadA3)") (class "Default")
      (node (ref "USB1") (pin "A3") (pinfunction "TX1-_A3") (pintype "passive"))
    )
    (net (code "109") (name "unconnected-(USB1-TX2+-PadB2)") (class "Default")
      (node (ref "USB1") (pin "B2") (pinfunction "TX2+_B2") (pintype "passive"))
    )
    (net (code "110") (name "unconnected-(USB1-TX2--PadB3)") (class "Default")
      (node (ref "USB1") (pin "B3") (pinfunction "TX2-_B3") (pintype "passive"))
    )
  )
)
